# Lixie_II_Reverse_LED.net
KiCad netlist of a schematic drawn in EAGLE
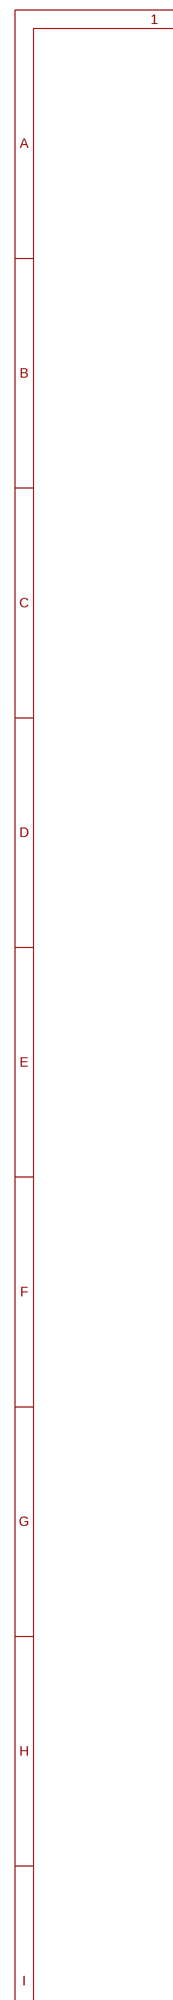
[diagram p0: schematic, sheet 1, part 1 of 2]
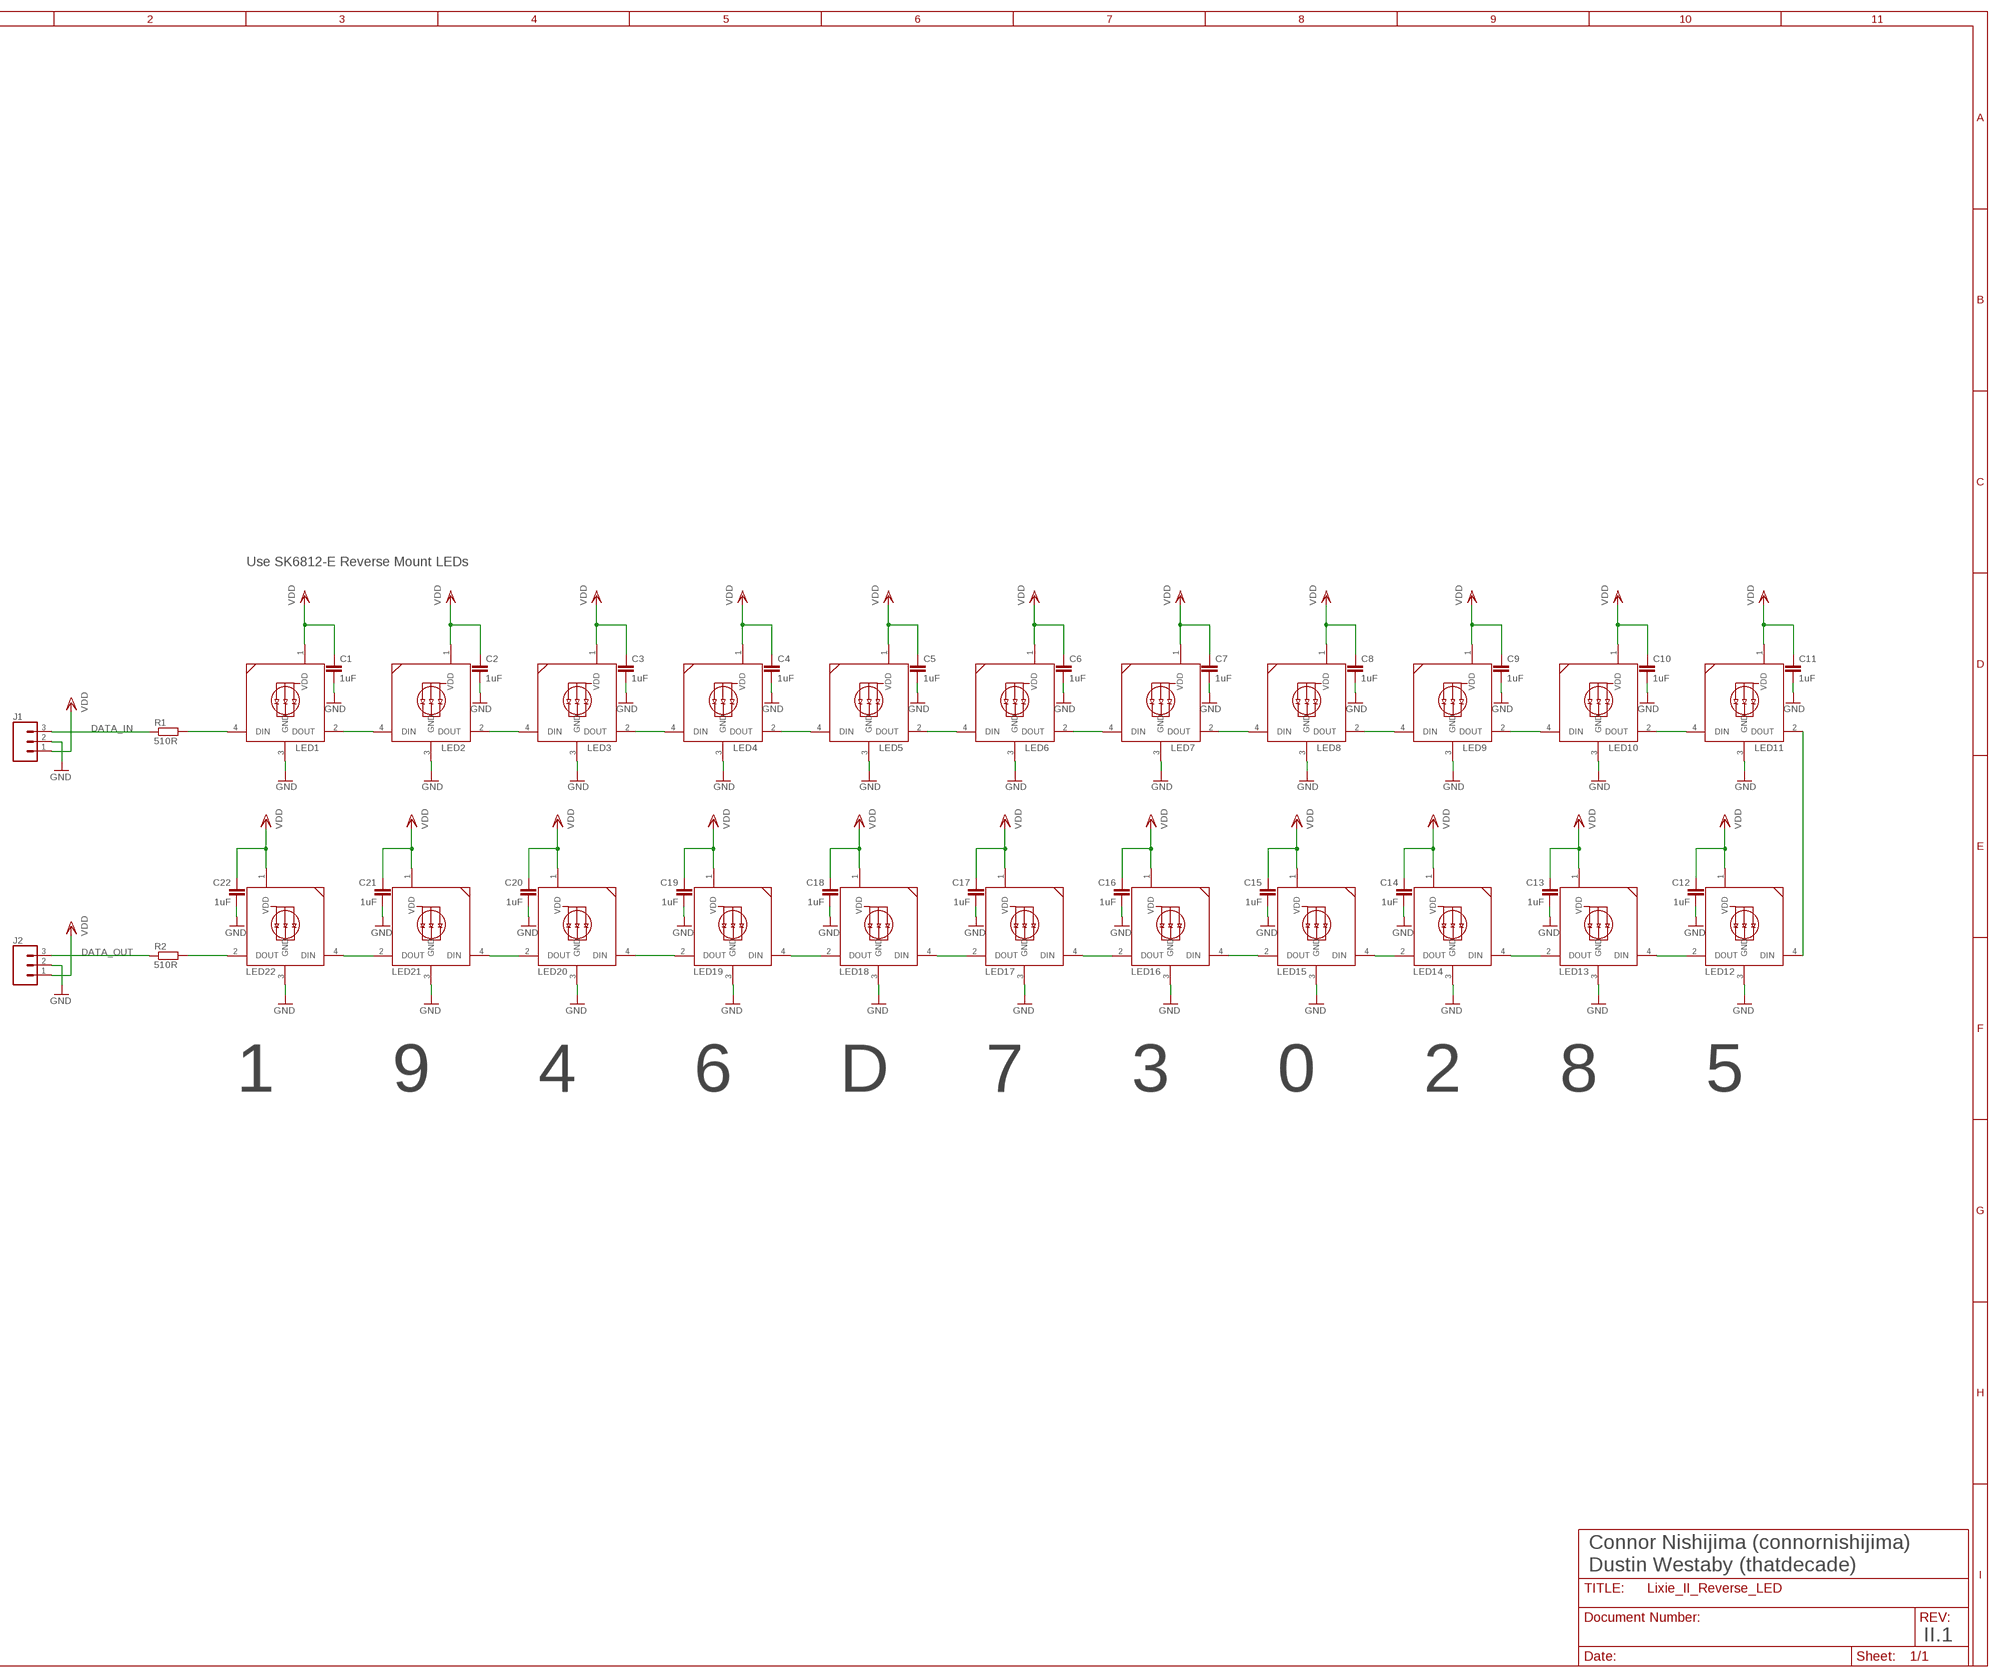
[diagram p1: schematic, sheet 1, part 2 of 2]

(export (version "E")
  (design (tool "Eeschema 10.0.6"))
  (components
    (comp (ref "C1")
      (value "1uF")
      (footprint "eagle-import:C0402")
      (fields (field (name "LCSC_PART") "C52923"))
      (libsource (lib "eagle-import") (part "C__04021UF/25V"))
    )
    (comp (ref "C2")
      (value "1uF")
      (footprint "eagle-import:C0402")
      (fields (field (name "LCSC_PART") "C52923"))
      (libsource (lib "eagle-import") (part "C__04021UF/25V"))
    )
    (comp (ref "C3")
      (value "1uF")
      (footprint "eagle-import:C0402")
      (fields (field (name "LCSC_PART") "C52923"))
      (libsource (lib "eagle-import") (part "C__04021UF/25V"))
    )
    (comp (ref "C4")
      (value "1uF")
      (footprint "eagle-import:C0402")
      (fields (field (name "LCSC_PART") "C52923"))
      (libsource (lib "eagle-import") (part "C__04021UF/25V"))
    )
    (comp (ref "C5")
      (value "1uF")
      (footprint "eagle-import:C0402")
      (fields (field (name "LCSC_PART") "C52923"))
      (libsource (lib "eagle-import") (part "C__04021UF/25V"))
    )
    (comp (ref "C6")
      (value "1uF")
      (footprint "eagle-import:C0402")
      (fields (field (name "LCSC_PART") "C52923"))
      (libsource (lib "eagle-import") (part "C__04021UF/25V"))
    )
    (comp (ref "C7")
      (value "1uF")
      (footprint "eagle-import:C0402")
      (fields (field (name "LCSC_PART") "C52923"))
      (libsource (lib "eagle-import") (part "C__04021UF/25V"))
    )
    (comp (ref "C8")
      (value "1uF")
      (footprint "eagle-import:C0402")
      (fields (field (name "LCSC_PART") "C52923"))
      (libsource (lib "eagle-import") (part "C__04021UF/25V"))
    )
    (comp (ref "C9")
      (value "1uF")
      (footprint "eagle-import:C0402")
      (fields (field (name "LCSC_PART") "C52923"))
      (libsource (lib "eagle-import") (part "C__04021UF/25V"))
    )
    (comp (ref "C10")
      (value "1uF")
      (footprint "eagle-import:C0402")
      (fields (field (name "LCSC_PART") "C52923"))
      (libsource (lib "eagle-import") (part "C__04021UF/25V"))
    )
    (comp (ref "C11")
      (value "1uF")
      (footprint "eagle-import:C0402")
      (fields (field (name "LCSC_PART") "C52923"))
      (libsource (lib "eagle-import") (part "C__04021UF/25V"))
    )
    (comp (ref "C12")
      (value "1uF")
      (footprint "eagle-import:C0402")
      (fields (field (name "LCSC_PART") "C52923"))
      (libsource (lib "eagle-import") (part "C__04021UF/25V"))
    )
    (comp (ref "C13")
      (value "1uF")
      (footprint "eagle-import:C0402")
      (fields (field (name "LCSC_PART") "C52923"))
      (libsource (lib "eagle-import") (part "C__04021UF/25V"))
    )
    (comp (ref "C14")
      (value "1uF")
      (footprint "eagle-import:C0402")
      (fields (field (name "LCSC_PART") "C52923"))
      (libsource (lib "eagle-import") (part "C__04021UF/25V"))
    )
    (comp (ref "C15")
      (value "1uF")
      (footprint "eagle-import:C0402")
      (fields (field (name "LCSC_PART") "C52923"))
      (libsource (lib "eagle-import") (part "C__04021UF/25V"))
    )
    (comp (ref "C16")
      (value "1uF")
      (footprint "eagle-import:C0402")
      (fields (field (name "LCSC_PART") "C52923"))
      (libsource (lib "eagle-import") (part "C__04021UF/25V"))
    )
    (comp (ref "C17")
      (value "1uF")
      (footprint "eagle-import:C0402")
      (fields (field (name "LCSC_PART") "C52923"))
      (libsource (lib "eagle-import") (part "C__04021UF/25V"))
    )
    (comp (ref "C18")
      (value "1uF")
      (footprint "eagle-import:C0402")
      (fields (field (name "LCSC_PART") "C52923"))
      (libsource (lib "eagle-import") (part "C__04021UF/25V"))
    )
    (comp (ref "C19")
      (value "1uF")
      (footprint "eagle-import:C0402")
      (fields (field (name "LCSC_PART") "C52923"))
      (libsource (lib "eagle-import") (part "C__04021UF/25V"))
    )
    (comp (ref "C20")
      (value "1uF")
      (footprint "eagle-import:C0402")
      (fields (field (name "LCSC_PART") "C52923"))
      (libsource (lib "eagle-import") (part "C__04021UF/25V"))
    )
    (comp (ref "C21")
      (value "1uF")
      (footprint "eagle-import:C0402")
      (fields (field (name "LCSC_PART") "C52923"))
      (libsource (lib "eagle-import") (part "C__04021UF/25V"))
    )
    (comp (ref "C22")
      (value "1uF")
      (footprint "eagle-import:C0402")
      (fields (field (name "LCSC_PART") "C52923"))
      (libsource (lib "eagle-import") (part "C__04021UF/25V"))
    )
    (comp (ref "J1")
      (value "CONN_031X03_NO_SILK")
      (footprint "eagle-import:1X03_NO_SILK")
      (libsource (lib "eagle-import") (part "CONN_031X03_NO_SILK"))
    )
    (comp (ref "J2")
      (value "CONN_031X03_NO_SILK")
      (footprint "eagle-import:1X03_NO_SILK")
      (libsource (lib "eagle-import") (part "CONN_031X03_NO_SILK"))
    )
    (comp (ref "LED1")
      (value "SK6812MINI_REV")
      (footprint "eagle-import:SK6812-E-SMD")
      (libsource (lib "eagle-import") (part "SK6812MINI_REV"))
    )
    (comp (ref "LED2")
      (value "SK6812MINI_REV")
      (footprint "eagle-import:SK6812-E-SMD")
      (libsource (lib "eagle-import") (part "SK6812MINI_REV"))
    )
    (comp (ref "LED3")
      (value "SK6812MINI_REV")
      (footprint "eagle-import:SK6812-E-SMD")
      (libsource (lib "eagle-import") (part "SK6812MINI_REV"))
    )
    (comp (ref "LED4")
      (value "SK6812MINI_REV")
      (footprint "eagle-import:SK6812-E-SMD")
      (libsource (lib "eagle-import") (part "SK6812MINI_REV"))
    )
    (comp (ref "LED5")
      (value "SK6812MINI_REV")
      (footprint "eagle-import:SK6812-E-SMD")
      (libsource (lib "eagle-import") (part "SK6812MINI_REV"))
    )
    (comp (ref "LED6")
      (value "SK6812MINI_REV")
      (footprint "eagle-import:SK6812-E-SMD")
      (libsource (lib "eagle-import") (part "SK6812MINI_REV"))
    )
    (comp (ref "LED7")
      (value "SK6812MINI_REV")
      (footprint "eagle-import:SK6812-E-SMD")
      (libsource (lib "eagle-import") (part "SK6812MINI_REV"))
    )
    (comp (ref "LED8")
      (value "SK6812MINI_REV")
      (footprint "eagle-import:SK6812-E-SMD")
      (libsource (lib "eagle-import") (part "SK6812MINI_REV"))
    )
    (comp (ref "LED9")
      (value "SK6812MINI_REV")
      (footprint "eagle-import:SK6812-E-SMD")
      (libsource (lib "eagle-import") (part "SK6812MINI_REV"))
    )
    (comp (ref "LED10")
      (value "SK6812MINI_REV")
      (footprint "eagle-import:SK6812-E-SMD")
      (libsource (lib "eagle-import") (part "SK6812MINI_REV"))
    )
    (comp (ref "LED11")
      (value "SK6812MINI_REV")
      (footprint "eagle-import:SK6812-E-SMD")
      (libsource (lib "eagle-import") (part "SK6812MINI_REV"))
    )
    (comp (ref "LED12")
      (value "SK6812MINI_REV")
      (footprint "eagle-import:SK6812-E-SMD")
      (libsource (lib "eagle-import") (part "SK6812MINI_REV"))
    )
    (comp (ref "LED13")
      (value "SK6812MINI_REV")
      (footprint "eagle-import:SK6812-E-SMD")
      (libsource (lib "eagle-import") (part "SK6812MINI_REV"))
    )
    (comp (ref "LED14")
      (value "SK6812MINI_REV")
      (footprint "eagle-import:SK6812-E-SMD")
      (libsource (lib "eagle-import") (part "SK6812MINI_REV"))
    )
    (comp (ref "LED15")
      (value "SK6812MINI_REV")
      (footprint "eagle-import:SK6812-E-SMD")
      (libsource (lib "eagle-import") (part "SK6812MINI_REV"))
    )
    (comp (ref "LED16")
      (value "SK6812MINI_REV")
      (footprint "eagle-import:SK6812-E-SMD")
      (libsource (lib "eagle-import") (part "SK6812MINI_REV"))
    )
    (comp (ref "LED17")
      (value "SK6812MINI_REV")
      (footprint "eagle-import:SK6812-E-SMD")
      (libsource (lib "eagle-import") (part "SK6812MINI_REV"))
    )
    (comp (ref "LED18")
      (value "SK6812MINI_REV")
      (footprint "eagle-import:SK6812-E-SMD")
      (libsource (lib "eagle-import") (part "SK6812MINI_REV"))
    )
    (comp (ref "LED19")
      (value "SK6812MINI_REV")
      (footprint "eagle-import:SK6812-E-SMD")
      (libsource (lib "eagle-import") (part "SK6812MINI_REV"))
    )
    (comp (ref "LED20")
      (value "SK6812MINI_REV")
      (footprint "eagle-import:SK6812-E-SMD")
      (libsource (lib "eagle-import") (part "SK6812MINI_REV"))
    )
    (comp (ref "LED21")
      (value "SK6812MINI_REV")
      (footprint "eagle-import:SK6812-E-SMD")
      (libsource (lib "eagle-import") (part "SK6812MINI_REV"))
    )
    (comp (ref "LED22")
      (value "SK6812MINI_REV")
      (footprint "eagle-import:SK6812-E-SMD")
      (libsource (lib "eagle-import") (part "SK6812MINI_REV"))
    )
    (comp (ref "R1")
      (value "510R")
      (footprint "eagle-import:R0402")
      (fields (field (name "LCSC_PART") "C25123"))
      (libsource (lib "eagle-import") (part "R__0402510R"))
    )
    (comp (ref "R2")
      (value "510R")
      (footprint "eagle-import:R0402")
      (fields (field (name "LCSC_PART") "C25123"))
      (libsource (lib "eagle-import") (part "R__0402510R"))
    )
  )
  (nets
    (net (code "1") (name "/DATA_IN") (class "Default")
      (node (ref "J1") (pin "3") (pinfunction "3_3") (pintype "passive"))
      (node (ref "R1") (pin "1") (pinfunction "1_1") (pintype "passive"))
    )
    (net (code "2") (name "/DATA_OUT") (class "Default")
      (node (ref "J2") (pin "3") (pinfunction "3_3") (pintype "passive"))
      (node (ref "R2") (pin "1") (pinfunction "1_1") (pintype "passive"))
    )
    (net (code "3") (name "GND") (class "Default")
      (node (ref "C1") (pin "2") (pinfunction "2_2") (pintype "passive"))
      (node (ref "C10") (pin "2") (pinfunction "2_2") (pintype "passive"))
      (node (ref "C11") (pin "2") (pinfunction "2_2") (pintype "passive"))
      (node (ref "C12") (pin "2") (pinfunction "2_2") (pintype "passive"))
      (node (ref "C13") (pin "2") (pinfunction "2_2") (pintype "passive"))
      (node (ref "C14") (pin "2") (pinfunction "2_2") (pintype "passive"))
      (node (ref "C15") (pin "2") (pinfunction "2_2") (pintype "passive"))
      (node (ref "C16") (pin "2") (pinfunction "2_2") (pintype "passive"))
      (node (ref "C17") (pin "2") (pinfunction "2_2") (pintype "passive"))
      (node (ref "C18") (pin "2") (pinfunction "2_2") (pintype "passive"))
      (node (ref "C19") (pin "2") (pinfunction "2_2") (pintype "passive"))
      (node (ref "C2") (pin "2") (pinfunction "2_2") (pintype "passive"))
      (node (ref "C20") (pin "2") (pinfunction "2_2") (pintype "passive"))
      (node (ref "C21") (pin "2") (pinfunction "2_2") (pintype "passive"))
      (node (ref "C22") (pin "2") (pinfunction "2_2") (pintype "passive"))
      (node (ref "C3") (pin "2") (pinfunction "2_2") (pintype "passive"))
      (node (ref "C4") (pin "2") (pinfunction "2_2") (pintype "passive"))
      (node (ref "C5") (pin "2") (pinfunction "2_2") (pintype "passive"))
      (node (ref "C6") (pin "2") (pinfunction "2_2") (pintype "passive"))
      (node (ref "C7") (pin "2") (pinfunction "2_2") (pintype "passive"))
      (node (ref "C8") (pin "2") (pinfunction "2_2") (pintype "passive"))
      (node (ref "C9") (pin "2") (pinfunction "2_2") (pintype "passive"))
      (node (ref "J1") (pin "2") (pinfunction "2_2") (pintype "passive"))
      (node (ref "J2") (pin "2") (pinfunction "2_2") (pintype "passive"))
      (node (ref "LED1") (pin "3") (pinfunction "GND_3") (pintype "bidirectional"))
      (node (ref "LED10") (pin "3") (pinfunction "GND_3") (pintype "bidirectional"))
      (node (ref "LED11") (pin "3") (pinfunction "GND_3") (pintype "bidirectional"))
      (node (ref "LED12") (pin "3") (pinfunction "GND_3") (pintype "bidirectional"))
      (node (ref "LED13") (pin "3") (pinfunction "GND_3") (pintype "bidirectional"))
      (node (ref "LED14") (pin "3") (pinfunction "GND_3") (pintype "bidirectional"))
      (node (ref "LED15") (pin "3") (pinfunction "GND_3") (pintype "bidirectional"))
      (node (ref "LED16") (pin "3") (pinfunction "GND_3") (pintype "bidirectional"))
      (node (ref "LED17") (pin "3") (pinfunction "GND_3") (pintype "bidirectional"))
      (node (ref "LED18") (pin "3") (pinfunction "GND_3") (pintype "bidirectional"))
      (node (ref "LED19") (pin "3") (pinfunction "GND_3") (pintype "bidirectional"))
      (node (ref "LED2") (pin "3") (pinfunction "GND_3") (pintype "bidirectional"))
      (node (ref "LED20") (pin "3") (pinfunction "GND_3") (pintype "bidirectional"))
      (node (ref "LED21") (pin "3") (pinfunction "GND_3") (pintype "bidirectional"))
      (node (ref "LED22") (pin "3") (pinfunction "GND_3") (pintype "bidirectional"))
      (node (ref "LED3") (pin "3") (pinfunction "GND_3") (pintype "bidirectional"))
      (node (ref "LED4") (pin "3") (pinfunction "GND_3") (pintype "bidirectional"))
      (node (ref "LED5") (pin "3") (pinfunction "GND_3") (pintype "bidirectional"))
      (node (ref "LED6") (pin "3") (pinfunction "GND_3") (pintype "bidirectional"))
      (node (ref "LED7") (pin "3") (pinfunction "GND_3") (pintype "bidirectional"))
      (node (ref "LED8") (pin "3") (pinfunction "GND_3") (pintype "bidirectional"))
      (node (ref "LED9") (pin "3") (pinfunction "GND_3") (pintype "bidirectional"))
    )
    (net (code "4") (name "Net-(LED1-DIN)") (class "Default")
      (node (ref "LED1") (pin "4") (pinfunction "DIN_4") (pintype "bidirectional"))
      (node (ref "R1") (pin "2") (pinfunction "2_2") (pintype "passive"))
    )
    (net (code "5") (name "Net-(LED1-DOUT)") (class "Default")
      (node (ref "LED1") (pin "2") (pinfunction "DOUT_2") (pintype "bidirectional"))
      (node (ref "LED2") (pin "4") (pinfunction "DIN_4") (pintype "bidirectional"))
    )
    (net (code "6") (name "Net-(LED2-DOUT)") (class "Default")
      (node (ref "LED2") (pin "2") (pinfunction "DOUT_2") (pintype "bidirectional"))
      (node (ref "LED3") (pin "4") (pinfunction "DIN_4") (pintype "bidirectional"))
    )
    (net (code "7") (name "Net-(LED3-DOUT)") (class "Default")
      (node (ref "LED3") (pin "2") (pinfunction "DOUT_2") (pintype "bidirectional"))
      (node (ref "LED4") (pin "4") (pinfunction "DIN_4") (pintype "bidirectional"))
    )
    (net (code "8") (name "Net-(LED4-DOUT)") (class "Default")
      (node (ref "LED4") (pin "2") (pinfunction "DOUT_2") (pintype "bidirectional"))
      (node (ref "LED5") (pin "4") (pinfunction "DIN_4") (pintype "bidirectional"))
    )
    (net (code "9") (name "Net-(LED5-DOUT)") (class "Default")
      (node (ref "LED5") (pin "2") (pinfunction "DOUT_2") (pintype "bidirectional"))
      (node (ref "LED6") (pin "4") (pinfunction "DIN_4") (pintype "bidirectional"))
    )
    (net (code "10") (name "Net-(LED6-DOUT)") (class "Default")
      (node (ref "LED6") (pin "2") (pinfunction "DOUT_2") (pintype "bidirectional"))
      (node (ref "LED7") (pin "4") (pinfunction "DIN_4") (pintype "bidirectional"))
    )
    (net (code "11") (name "Net-(LED7-DOUT)") (class "Default")
      (node (ref "LED7") (pin "2") (pinfunction "DOUT_2") (pintype "bidirectional"))
      (node (ref "LED8") (pin "4") (pinfunction "DIN_4") (pintype "bidirectional"))
    )
    (net (code "12") (name "Net-(LED8-DOUT)") (class "Default")
      (node (ref "LED8") (pin "2") (pinfunction "DOUT_2") (pintype "bidirectional"))
      (node (ref "LED9") (pin "4") (pinfunction "DIN_4") (pintype "bidirectional"))
    )
    (net (code "13") (name "Net-(LED10-DIN)") (class "Default")
      (node (ref "LED10") (pin "4") (pinfunction "DIN_4") (pintype "bidirectional"))
      (node (ref "LED9") (pin "2") (pinfunction "DOUT_2") (pintype "bidirectional"))
    )
    (net (code "14") (name "Net-(LED10-DOUT)") (class "Default")
      (node (ref "LED10") (pin "2") (pinfunction "DOUT_2") (pintype "bidirectional"))
      (node (ref "LED11") (pin "4") (pinfunction "DIN_4") (pintype "bidirectional"))
    )
    (net (code "15") (name "Net-(LED11-DOUT)") (class "Default")
      (node (ref "LED11") (pin "2") (pinfunction "DOUT_2") (pintype "bidirectional"))
      (node (ref "LED12") (pin "4") (pinfunction "DIN_4") (pintype "bidirectional"))
    )
    (net (code "16") (name "Net-(LED12-DOUT)") (class "Default")
      (node (ref "LED12") (pin "2") (pinfunction "DOUT_2") (pintype "bidirectional"))
      (node (ref "LED13") (pin "4") (pinfunction "DIN_4") (pintype "bidirectional"))
    )
    (net (code "17") (name "Net-(LED13-DOUT)") (class "Default")
      (node (ref "LED13") (pin "2") (pinfunction "DOUT_2") (pintype "bidirectional"))
      (node (ref "LED14") (pin "4") (pinfunction "DIN_4") (pintype "bidirectional"))
    )
    (net (code "18") (name "Net-(LED14-DOUT)") (class "Default")
      (node (ref "LED14") (pin "2") (pinfunction "DOUT_2") (pintype "bidirectional"))
      (node (ref "LED15") (pin "4") (pinfunction "DIN_4") (pintype "bidirectional"))
    )
    (net (code "19") (name "Net-(LED15-DOUT)") (class "Default")
      (node (ref "LED15") (pin "2") (pinfunction "DOUT_2") (pintype "bidirectional"))
      (node (ref "LED16") (pin "4") (pinfunction "DIN_4") (pintype "bidirectional"))
    )
    (net (code "20") (name "Net-(LED16-DOUT)") (class "Default")
      (node (ref "LED16") (pin "2") (pinfunction "DOUT_2") (pintype "bidirectional"))
      (node (ref "LED17") (pin "4") (pinfunction "DIN_4") (pintype "bidirectional"))
    )
    (net (code "21") (name "Net-(LED17-DOUT)") (class "Default")
      (node (ref "LED17") (pin "2") (pinfunction "DOUT_2") (pintype "bidirectional"))
      (node (ref "LED18") (pin "4") (pinfunction "DIN_4") (pintype "bidirectional"))
    )
    (net (code "22") (name "Net-(LED18-DOUT)") (class "Default")
      (node (ref "LED18") (pin "2") (pinfunction "DOUT_2") (pintype "bidirectional"))
      (node (ref "LED19") (pin "4") (pinfunction "DIN_4") (pintype "bidirectional"))
    )
    (net (code "23") (name "Net-(LED19-DOUT)") (class "Default")
      (node (ref "LED19") (pin "2") (pinfunction "DOUT_2") (pintype "bidirectional"))
      (node (ref "LED20") (pin "4") (pinfunction "DIN_4") (pintype "bidirectional"))
    )
    (net (code "24") (name "Net-(LED20-DOUT)") (class "Default")
      (node (ref "LED20") (pin "2") (pinfunction "DOUT_2") (pintype "bidirectional"))
      (node (ref "LED21") (pin "4") (pinfunction "DIN_4") (pintype "bidirectional"))
    )
    (net (code "25") (name "Net-(LED21-DOUT)") (class "Default")
      (node (ref "LED21") (pin "2") (pinfunction "DOUT_2") (pintype "bidirectional"))
      (node (ref "LED22") (pin "4") (pinfunction "DIN_4") (pintype "bidirectional"))
    )
    (net (code "26") (name "Net-(LED22-DOUT)") (class "Default")
      (node (ref "LED22") (pin "2") (pinfunction "DOUT_2") (pintype "bidirectional"))
      (node (ref "R2") (pin "2") (pinfunction "2_2") (pintype "passive"))
    )
    (net (code "27") (name "VDD") (class "Default")
      (node (ref "C1") (pin "1") (pinfunction "1_1") (pintype "passive"))
      (node (ref "C10") (pin "1") (pinfunction "1_1") (pintype "passive"))
      (node (ref "C11") (pin "1") (pinfunction "1_1") (pintype "passive"))
      (node (ref "C12") (pin "1") (pinfunction "1_1") (pintype "passive"))
      (node (ref "C13") (pin "1") (pinfunction "1_1") (pintype "passive"))
      (node (ref "C14") (pin "1") (pinfunction "1_1") (pintype "passive"))
      (node (ref "C15") (pin "1") (pinfunction "1_1") (pintype "passive"))
      (node (ref "C16") (pin "1") (pinfunction "1_1") (pintype "passive"))
      (node (ref "C17") (pin "1") (pinfunction "1_1") (pintype "passive"))
      (node (ref "C18") (pin "1") (pinfunction "1_1") (pintype "passive"))
      (node (ref "C19") (pin "1") (pinfunction "1_1") (pintype "passive"))
      (node (ref "C2") (pin "1") (pinfunction "1_1") (pintype "passive"))
      (node (ref "C20") (pin "1") (pinfunction "1_1") (pintype "passive"))
      (node (ref "C21") (pin "1") (pinfunction "1_1") (pintype "passive"))
      (node (ref "C22") (pin "1") (pinfunction "1_1") (pintype "passive"))
      (node (ref "C3") (pin "1") (pinfunction "1_1") (pintype "passive"))
      (node (ref "C4") (pin "1") (pinfunction "1_1") (pintype "passive"))
      (node (ref "C5") (pin "1") (pinfunction "1_1") (pintype "passive"))
      (node (ref "C6") (pin "1") (pinfunction "1_1") (pintype "passive"))
      (node (ref "C7") (pin "1") (pinfunction "1_1") (pintype "passive"))
      (node (ref "C8") (pin "1") (pinfunction "1_1") (pintype "passive"))
      (node (ref "C9") (pin "1") (pinfunction "1_1") (pintype "passive"))
      (node (ref "J1") (pin "1") (pinfunction "1_1") (pintype "passive"))
      (node (ref "J2") (pin "1") (pinfunction "1_1") (pintype "passive"))
      (node (ref "LED1") (pin "1") (pinfunction "VDD_1") (pintype "bidirectional"))
      (node (ref "LED10") (pin "1") (pinfunction "VDD_1") (pintype "bidirectional"))
      (node (ref "LED11") (pin "1") (pinfunction "VDD_1") (pintype "bidirectional"))
      (node (ref "LED12") (pin "1") (pinfunction "VDD_1") (pintype "bidirectional"))
      (node (ref "LED13") (pin "1") (pinfunction "VDD_1") (pintype "bidirectional"))
      (node (ref "LED14") (pin "1") (pinfunction "VDD_1") (pintype "bidirectional"))
      (node (ref "LED15") (pin "1") (pinfunction "VDD_1") (pintype "bidirectional"))
      (node (ref "LED16") (pin "1") (pinfunction "VDD_1") (pintype "bidirectional"))
      (node (ref "LED17") (pin "1") (pinfunction "VDD_1") (pintype "bidirectional"))
      (node (ref "LED18") (pin "1") (pinfunction "VDD_1") (pintype "bidirectional"))
      (node (ref "LED19") (pin "1") (pinfunction "VDD_1") (pintype "bidirectional"))
      (node (ref "LED2") (pin "1") (pinfunction "VDD_1") (pintype "bidirectional"))
      (node (ref "LED20") (pin "1") (pinfunction "VDD_1") (pintype "bidirectional"))
      (node (ref "LED21") (pin "1") (pinfunction "VDD_1") (pintype "bidirectional"))
      (node (ref "LED22") (pin "1") (pinfunction "VDD_1") (pintype "bidirectional"))
      (node (ref "LED3") (pin "1") (pinfunction "VDD_1") (pintype "bidirectional"))
      (node (ref "LED4") (pin "1") (pinfunction "VDD_1") (pintype "bidirectional"))
      (node (ref "LED5") (pin "1") (pinfunction "VDD_1") (pintype "bidirectional"))
      (node (ref "LED6") (pin "1") (pinfunction "VDD_1") (pintype "bidirectional"))
      (node (ref "LED7") (pin "1") (pinfunction "VDD_1") (pintype "bidirectional"))
      (node (ref "LED8") (pin "1") (pinfunction "VDD_1") (pintype "bidirectional"))
      (node (ref "LED9") (pin "1") (pinfunction "VDD_1") (pintype "bidirectional"))
    )
  )
)
